# PCB_3U_Tester.net
KiCad netlist of a schematic drawn in Altium Designer
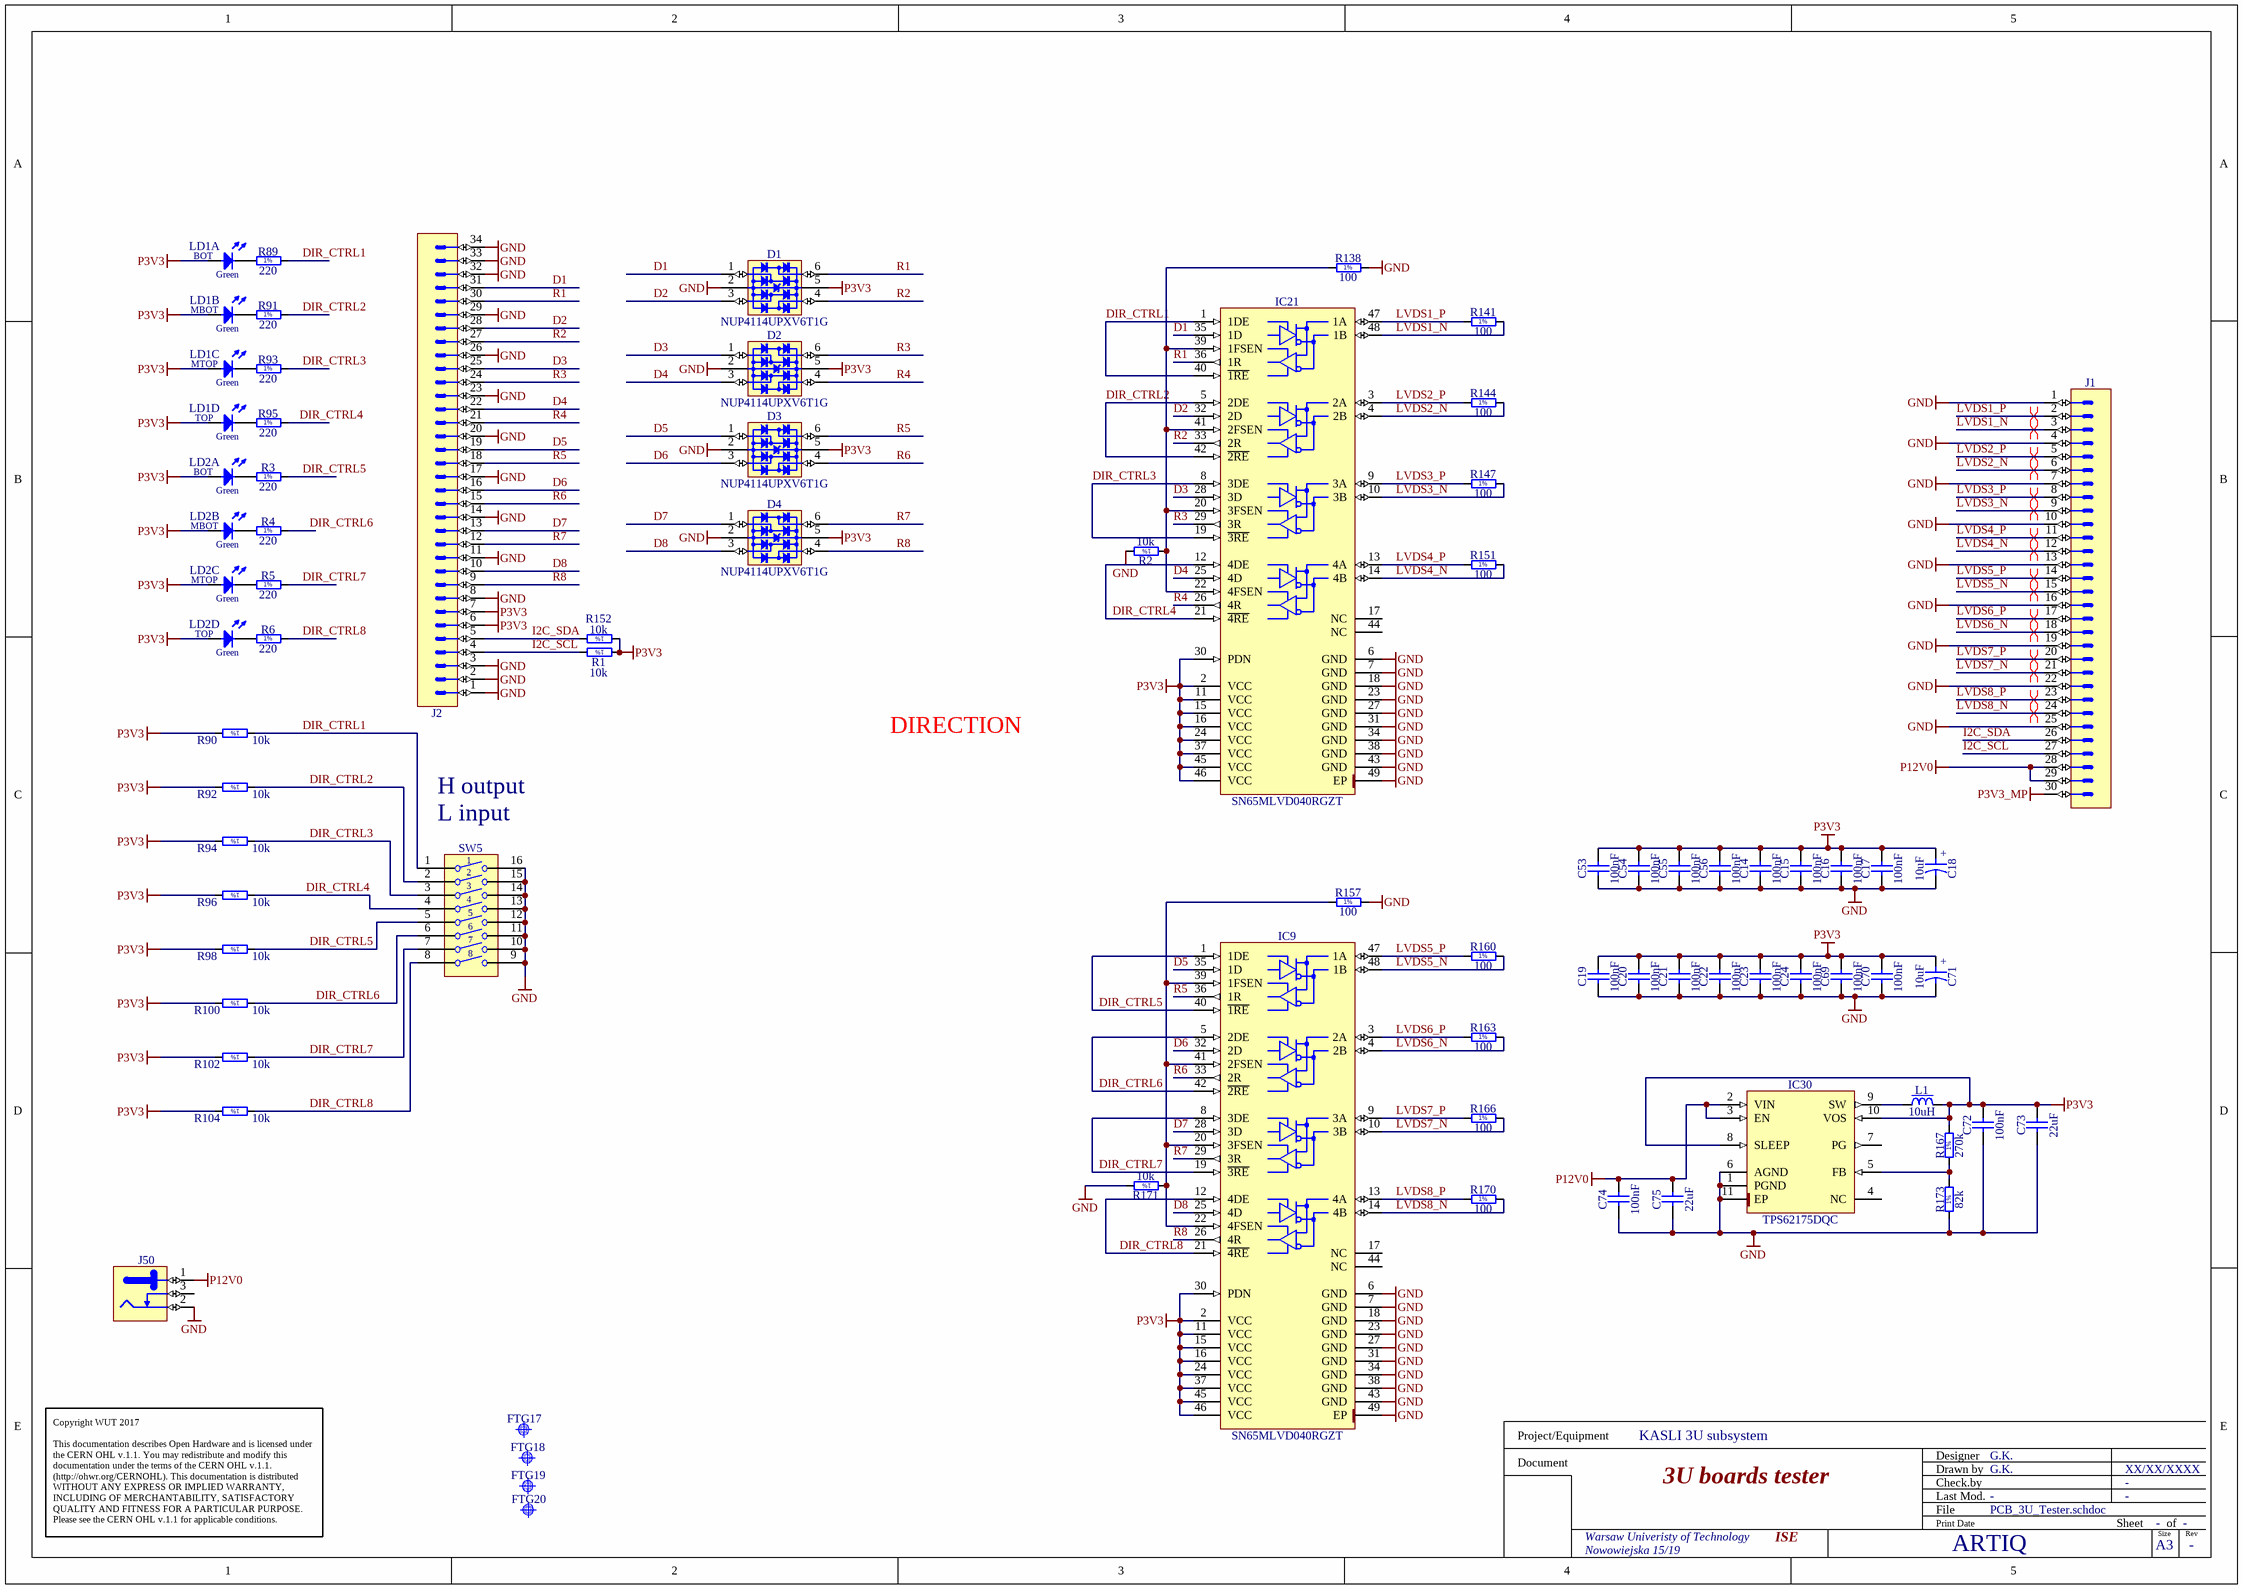
[diagram p0: PCB_3U_Tester.schdoc]

(export (version "E")
  (design (tool "Eeschema 10.0.6"))
  (components
    (comp (ref "C14")
      (value "100nF")
      (footprint "CAPC1005X55N")
      (description "Non-polarised capacitor")
      (fields
        (field (name "PART NUMBER") "CC0402_100NF_16V_10%_X5R")
        (field (name "VOLTAGE") "16V")
        (field (name "AUTHOR") "CERN DEM JLC")
      )
      (libsource (lib "Capacitors") (part "Capacitor - non polarized"))
    )
    (comp (ref "C15")
      (value "100nF")
      (footprint "CAPC1005X55N")
      (description "Non-polarised capacitor")
      (fields
        (field (name "PART NUMBER") "CC0402_100NF_16V_10%_X5R")
        (field (name "VOLTAGE") "16V")
        (field (name "AUTHOR") "CERN DEM JLC")
      )
      (libsource (lib "Capacitors") (part "Capacitor - non polarized"))
    )
    (comp (ref "C16")
      (value "100nF")
      (footprint "CAPC1005X55N")
      (description "Non-polarised capacitor")
      (fields
        (field (name "PART NUMBER") "CC0402_100NF_16V_10%_X5R")
        (field (name "VOLTAGE") "16V")
        (field (name "AUTHOR") "CERN DEM JLC")
      )
      (libsource (lib "Capacitors") (part "Capacitor - non polarized"))
    )
    (comp (ref "C17")
      (value "100nF")
      (footprint "CAPC1005X55N")
      (description "Non-polarised capacitor")
      (fields
        (field (name "PART NUMBER") "CC0402_100NF_16V_10%_X5R")
        (field (name "VOLTAGE") "16V")
        (field (name "AUTHOR") "CERN DEM JLC")
      )
      (libsource (lib "Capacitors") (part "Capacitor - non polarized"))
    )
    (comp (ref "C18")
      (value "10uF")
      (footprint "CAPAE430X540N")
      (description "Polarised capacitor")
      (fields
        (field (name "PART NUMBER") "CAE430-540_10UF_16V_20%")
        (field (name "VOLTAGE") "16V")
        (field (name "AUTHOR") "CERN DEM JLC")
      )
      (libsource (lib "Capacitors") (part "Capacitor - polarized"))
    )
    (comp (ref "C19")
      (value "100nF")
      (footprint "CAPC1005X55N")
      (description "Non-polarised capacitor")
      (fields
        (field (name "PART NUMBER") "CC0402_100NF_16V_10%_X5R")
        (field (name "VOLTAGE") "16V")
        (field (name "AUTHOR") "CERN DEM JLC")
      )
      (libsource (lib "Capacitors") (part "Capacitor - non polarized"))
    )
    (comp (ref "C20")
      (value "100nF")
      (footprint "CAPC1005X55N")
      (description "Non-polarised capacitor")
      (fields
        (field (name "PART NUMBER") "CC0402_100NF_16V_10%_X5R")
        (field (name "VOLTAGE") "16V")
        (field (name "AUTHOR") "CERN DEM JLC")
      )
      (libsource (lib "Capacitors") (part "Capacitor - non polarized"))
    )
    (comp (ref "C21")
      (value "100nF")
      (footprint "CAPC1005X55N")
      (description "Non-polarised capacitor")
      (fields
        (field (name "PART NUMBER") "CC0402_100NF_16V_10%_X5R")
        (field (name "VOLTAGE") "16V")
        (field (name "AUTHOR") "CERN DEM JLC")
      )
      (libsource (lib "Capacitors") (part "Capacitor - non polarized"))
    )
    (comp (ref "C22")
      (value "100nF")
      (footprint "CAPC1005X55N")
      (description "Non-polarised capacitor")
      (fields
        (field (name "PART NUMBER") "CC0402_100NF_16V_10%_X5R")
        (field (name "VOLTAGE") "16V")
        (field (name "AUTHOR") "CERN DEM JLC")
      )
      (libsource (lib "Capacitors") (part "Capacitor - non polarized"))
    )
    (comp (ref "C23")
      (value "100nF")
      (footprint "CAPC1005X55N")
      (description "Non-polarised capacitor")
      (fields
        (field (name "PART NUMBER") "CC0402_100NF_16V_10%_X5R")
        (field (name "VOLTAGE") "16V")
        (field (name "AUTHOR") "CERN DEM JLC")
      )
      (libsource (lib "Capacitors") (part "Capacitor - non polarized"))
    )
    (comp (ref "C24")
      (value "100nF")
      (footprint "CAPC1005X55N")
      (description "Non-polarised capacitor")
      (fields
        (field (name "PART NUMBER") "CC0402_100NF_16V_10%_X5R")
        (field (name "VOLTAGE") "16V")
        (field (name "AUTHOR") "CERN DEM JLC")
      )
      (libsource (lib "Capacitors") (part "Capacitor - non polarized"))
    )
    (comp (ref "C53")
      (value "100nF")
      (footprint "CAPC1005X55N")
      (description "Non-polarised capacitor")
      (fields
        (field (name "PART NUMBER") "CC0402_100NF_16V_10%_X5R")
        (field (name "VOLTAGE") "16V")
        (field (name "AUTHOR") "CERN DEM JLC")
      )
      (libsource (lib "Capacitors") (part "Capacitor - non polarized"))
    )
    (comp (ref "C54")
      (value "100nF")
      (footprint "CAPC1005X55N")
      (description "Non-polarised capacitor")
      (fields
        (field (name "PART NUMBER") "CC0402_100NF_16V_10%_X5R")
        (field (name "VOLTAGE") "16V")
        (field (name "AUTHOR") "CERN DEM JLC")
      )
      (libsource (lib "Capacitors") (part "Capacitor - non polarized"))
    )
    (comp (ref "C55")
      (value "100nF")
      (footprint "CAPC1005X55N")
      (description "Non-polarised capacitor")
      (fields
        (field (name "PART NUMBER") "CC0402_100NF_16V_10%_X5R")
        (field (name "VOLTAGE") "16V")
        (field (name "AUTHOR") "CERN DEM JLC")
      )
      (libsource (lib "Capacitors") (part "Capacitor - non polarized"))
    )
    (comp (ref "C56")
      (value "100nF")
      (footprint "CAPC1005X55N")
      (description "Non-polarised capacitor")
      (fields
        (field (name "PART NUMBER") "CC0402_100NF_16V_10%_X5R")
        (field (name "VOLTAGE") "16V")
        (field (name "AUTHOR") "CERN DEM JLC")
      )
      (libsource (lib "Capacitors") (part "Capacitor - non polarized"))
    )
    (comp (ref "C69")
      (value "100nF")
      (footprint "CAPC1005X55N")
      (description "Non-polarised capacitor")
      (fields
        (field (name "PART NUMBER") "CC0402_100NF_16V_10%_X5R")
        (field (name "VOLTAGE") "16V")
        (field (name "AUTHOR") "CERN DEM JLC")
      )
      (libsource (lib "Capacitors") (part "Capacitor - non polarized"))
    )
    (comp (ref "C70")
      (value "100nF")
      (footprint "CAPC1005X55N")
      (description "Non-polarised capacitor")
      (fields
        (field (name "PART NUMBER") "CC0402_100NF_16V_10%_X5R")
        (field (name "VOLTAGE") "16V")
        (field (name "AUTHOR") "CERN DEM JLC")
      )
      (libsource (lib "Capacitors") (part "Capacitor - non polarized"))
    )
    (comp (ref "C71")
      (value "10uF")
      (footprint "CAPAE430X540N")
      (description "Polarised capacitor")
      (fields
        (field (name "PART NUMBER") "CAE430-540_10UF_16V_20%")
        (field (name "VOLTAGE") "16V")
        (field (name "AUTHOR") "CERN DEM JLC")
      )
      (libsource (lib "Capacitors") (part "Capacitor - polarized"))
    )
    (comp (ref "C72")
      (value "100nF")
      (footprint "CAPC1005X55N")
      (description "Non-polarised capacitor")
      (fields
        (field (name "PART NUMBER") "CC0402_100NF_16V_10%_X5R")
        (field (name "VOLTAGE") "16V")
        (field (name "AUTHOR") "CERN DEM JLC")
      )
      (libsource (lib "Capacitors") (part "Capacitor - non polarized"))
    )
    (comp (ref "C73")
      (value "22uF")
      (footprint "CAPC2012X135N")
      (description "Non-polarised capacitor")
      (fields
        (field (name "PART NUMBER") "CC0805_22UF_16V_10%_X5R")
        (field (name "VOLTAGE") "16V")
        (field (name "AUTHOR") "CERN DEM JLC")
      )
      (libsource (lib "Capacitors") (part "Capacitor - non polarized"))
    )
    (comp (ref "C74")
      (value "100nF")
      (footprint "CAPC1005X55N")
      (description "Non-polarised capacitor")
      (fields
        (field (name "PART NUMBER") "CC0402_100NF_16V_10%_X5R")
        (field (name "VOLTAGE") "16V")
        (field (name "AUTHOR") "CERN DEM JLC")
      )
      (libsource (lib "Capacitors") (part "Capacitor - non polarized"))
    )
    (comp (ref "C75")
      (value "22uF")
      (footprint "CAPC2012X135N")
      (description "Non-polarised capacitor")
      (fields
        (field (name "PART NUMBER") "CC0805_22UF_16V_10%_X5R")
        (field (name "VOLTAGE") "16V")
        (field (name "AUTHOR") "CERN DEM JLC")
      )
      (libsource (lib "Capacitors") (part "Capacitor - non polarized"))
    )
    (comp (ref "D1")
      (value "NUP4114UPXV6T1G")
      (footprint "SOTFL50P160X60-6N")
      (fields
        (field (name "VOLTAGE") "5.5V")
        (field (name "MANUFACTURER") "ON SEMICONDUCTOR")
        (field (name "AUTHOR") "CERN DEM JLC")
      )
      (libsource (lib "ICs And Semiconductors") (part "NUP4114"))
    )
    (comp (ref "D2")
      (value "NUP4114UPXV6T1G")
      (footprint "SOTFL50P160X60-6N")
      (fields
        (field (name "VOLTAGE") "5.5V")
        (field (name "MANUFACTURER") "ON SEMICONDUCTOR")
        (field (name "AUTHOR") "CERN DEM JLC")
      )
      (libsource (lib "ICs And Semiconductors") (part "NUP4114"))
    )
    (comp (ref "D3")
      (value "NUP4114UPXV6T1G")
      (footprint "SOTFL50P160X60-6N")
      (fields
        (field (name "VOLTAGE") "5.5V")
        (field (name "MANUFACTURER") "ON SEMICONDUCTOR")
        (field (name "AUTHOR") "CERN DEM JLC")
      )
      (libsource (lib "ICs And Semiconductors") (part "NUP4114"))
    )
    (comp (ref "D4")
      (value "NUP4114UPXV6T1G")
      (footprint "SOTFL50P160X60-6N")
      (fields
        (field (name "VOLTAGE") "5.5V")
        (field (name "MANUFACTURER") "ON SEMICONDUCTOR")
        (field (name "AUTHOR") "CERN DEM JLC")
      )
      (libsource (lib "ICs And Semiconductors") (part "NUP4114"))
    )
    (comp (ref "FTG17")
      (value "Use only in PCB")
      (footprint "FIDUCIAL_TOP_C100-200")
      (description "Fiducial Target")
      (fields (field (name "PART NUMBER") "FIDUCIAL_TARGET_C100-200") (field (name "AUTHOR") "CERN DEM JLC"))
      (libsource (lib "Eletro-mechanical") (part "Fiducial Target"))
    )
    (comp (ref "FTG18")
      (value "Use only in PCB")
      (footprint "FIDUCIAL_TOP_S100-200")
      (description "Fiducial Target")
      (fields (field (name "PART NUMBER") "FIDUCIAL_TARGET_S100-200") (field (name "AUTHOR") "CERN DEM JLC"))
      (libsource (lib "Eletro-mechanical") (part "Fiducial Target"))
    )
    (comp (ref "FTG19")
      (value "Use only in PCB")
      (footprint "FIDUCIAL_TOP_S200-400")
      (description "Fiducial Target")
      (fields (field (name "PART NUMBER") "FIDUCIAL_TARGET_S200-400") (field (name "AUTHOR") "CERN DEM JLC"))
      (libsource (lib "Eletro-mechanical") (part "Fiducial Target"))
    )
    (comp (ref "FTG20")
      (value "Use only in PCB")
      (footprint "FIDUCIAL_TOP_S100-200")
      (description "Fiducial Target")
      (fields (field (name "PART NUMBER") "FIDUCIAL_TARGET_S100-200") (field (name "AUTHOR") "CERN DEM JLC"))
      (libsource (lib "Eletro-mechanical") (part "Fiducial Target"))
    )
    (comp (ref "IC9")
      (value "SN65MLVD040RGZT")
      (footprint "QFN50P700X700X100-49N-S420")
      (description "4-Channel Half-Duplex M-LVDS Line Transceiver")
      (fields (field (name "MANUFACTURER") "TEXAS INSTRUMENTS") (field (name "AUTHOR") "CERN DEM JLC"))
      (libsource (lib "ICs And Semiconductors") (part "SN65MLVD040"))
    )
    (comp (ref "IC21")
      (value "SN65MLVD040RGZT")
      (footprint "QFN50P700X700X100-49N-S420")
      (description "4-Channel Half-Duplex M-LVDS Line Transceiver")
      (fields (field (name "MANUFACTURER") "TEXAS INSTRUMENTS") (field (name "AUTHOR") "CERN DEM JLC"))
      (libsource (lib "ICs And Semiconductors") (part "SN65MLVD040"))
    )
    (comp (ref "IC30")
      (value "TPS62175DQC")
      (footprint "SON50P200X300X80-11N-R94X250")
      (description "4.75-28VDC to 1-6VDC, 500mA Step-Down Converter With Sleep Mode")
      (fields (field (name "MANUFACTURER") "TEXAS INSTRUMENTS") (field (name "AUTHOR") "CERN DEM JMW"))
      (libsource (lib "ICs And Semiconductors") (part "TPS62175"))
    )
    (comp (ref "J1")
      (value "~")
      (footprint "3M_N2530-6002RB")
      (description "Connector 30 Male")
      (fields
        (field (name "PART NUMBER") "3M_N2530-6002RB")
        (field (name "MANUFACTURER") "3M")
        (field (name "AUTHOR") "CERN DEM JLC")
      )
      (libsource (lib "Connectors") (part "Connector 30 Male"))
    )
    (comp (ref "J2")
      (value "Header 34")
      (footprint "3M_N2534-5002RB")
      (description "Connector 34 Male")
      (fields
        (field (name "PART NUMBER") "3M_N2534-5002RB")
        (field (name "MANUFACTURER") "3M")
        (field (name "AUTHOR") "CERN DEM JLC")
      )
      (libsource (lib "Connectors") (part "Connector 34 Male"))
    )
    (comp (ref "J50")
      (value "Jack")
      (footprint "CUI_PJ-102BH")
      (description "2.5 mm Center Pin, 5A, 24V Right Angle, Through Hole, Tapered Pins, DC Power Jack Connector")
      (fields
        (field (name "PART NUMBER") "CUI_PJ-102BH")
        (field (name "MANUFACTURER") "CUI INC.")
        (field (name "AUTHOR") "CERN DEM JLC")
      )
      (libsource (lib "Connectors") (part "CUI_PJ-102BH"))
    )
    (comp (ref "L1")
      (value "10uH")
      (footprint "IND_MURATA-PS_8400")
      (description "Inductor With Core")
      (fields
        (field (name "PART NUMBER") "IND_10UH_10%_MURATA-PS_8400")
        (field (name "POWER") "950mA")
        (field (name "AUTHOR") "CERN DEM JLC")
      )
      (libsource (lib "Inductors & Transformers") (part "Inductor With Magnetic core"))
    )
    (comp (ref "LD1")
      (value "Green")
      (footprint "LED_BIVAR_H485CGDL")
      (description "LED x4 Green 1C2A-BOT_3C4A_5C6A_7C8A-TOP")
      (fields
        (field (name "PART NUMBER") "LED_BIVAR_H485CGDL")
        (field (name "MANUFACTURER") "BIVAR")
        (field (name "AUTHOR") "CERN DEM JLC")
      )
      (libsource (lib "ICs And Semiconductors") (part "LED x4 Green 1C2A-BOT_3C4A_5C6A_7C8A-TOP"))
    )
    (comp (ref "LD2")
      (value "Green")
      (footprint "LED_BIVAR_H485CGDL")
      (description "LED x4 Green 1C2A-BOT_3C4A_5C6A_7C8A-TOP")
      (fields
        (field (name "PART NUMBER") "LED_BIVAR_H485CGDL")
        (field (name "MANUFACTURER") "BIVAR")
        (field (name "AUTHOR") "CERN DEM JLC")
      )
      (libsource (lib "ICs And Semiconductors") (part "LED x4 Green 1C2A-BOT_3C4A_5C6A_7C8A-TOP"))
    )
    (comp (ref "R1")
      (value "10k")
      (footprint "RESC1005X40N")
      (description "Resistor - 1%")
      (fields
        (field (name "PART NUMBER") "R0402_10K_1%_0.0625W_100PPM")
        (field (name "POWER") "0.0625W")
        (field (name "AUTHOR") "CERN DEM JLC")
      )
      (libsource (lib "Resistors") (part "Resistor - 1%"))
    )
    (comp (ref "R2")
      (value "10k")
      (footprint "RESC1005X40N")
      (description "Resistor - 1%")
      (fields
        (field (name "PART NUMBER") "R0402_10K_1%_0.0625W_100PPM")
        (field (name "POWER") "0.0625W")
        (field (name "AUTHOR") "CERN DEM JLC")
      )
      (libsource (lib "Resistors") (part "Resistor - 1%"))
    )
    (comp (ref "R3")
      (value "220")
      (footprint "RESC1608X55N")
      (description "Resistor - 1%")
      (fields
        (field (name "PART NUMBER") "R0603_220R_1%_0.1W_100PPM")
        (field (name "POWER") "0.1W")
        (field (name "AUTHOR") "CERN DEM JLC")
      )
      (libsource (lib "Resistors") (part "Resistor - 1%"))
    )
    (comp (ref "R4")
      (value "220")
      (footprint "RESC1608X55N")
      (description "Resistor - 1%")
      (fields
        (field (name "PART NUMBER") "R0603_220R_1%_0.1W_100PPM")
        (field (name "POWER") "0.1W")
        (field (name "AUTHOR") "CERN DEM JLC")
      )
      (libsource (lib "Resistors") (part "Resistor - 1%"))
    )
    (comp (ref "R5")
      (value "220")
      (footprint "RESC1608X55N")
      (description "Resistor - 1%")
      (fields
        (field (name "PART NUMBER") "R0603_220R_1%_0.1W_100PPM")
        (field (name "POWER") "0.1W")
        (field (name "AUTHOR") "CERN DEM JLC")
      )
      (libsource (lib "Resistors") (part "Resistor - 1%"))
    )
    (comp (ref "R6")
      (value "220")
      (footprint "RESC1608X55N")
      (description "Resistor - 1%")
      (fields
        (field (name "PART NUMBER") "R0603_220R_1%_0.1W_100PPM")
        (field (name "POWER") "0.1W")
        (field (name "AUTHOR") "CERN DEM JLC")
      )
      (libsource (lib "Resistors") (part "Resistor - 1%"))
    )
    (comp (ref "R89")
      (value "220")
      (footprint "RESC1608X55N")
      (description "Resistor - 1%")
      (fields
        (field (name "PART NUMBER") "R0603_220R_1%_0.1W_100PPM")
        (field (name "POWER") "0.1W")
        (field (name "AUTHOR") "CERN DEM JLC")
      )
      (libsource (lib "Resistors") (part "Resistor - 1%"))
    )
    (comp (ref "R90")
      (value "10k")
      (footprint "RESC1005X40N")
      (description "Resistor - 1%")
      (fields
        (field (name "PART NUMBER") "R0402_10K_1%_0.0625W_100PPM")
        (field (name "POWER") "0.0625W")
        (field (name "AUTHOR") "CERN DEM JLC")
      )
      (libsource (lib "Resistors") (part "Resistor - 1%"))
    )
    (comp (ref "R91")
      (value "220")
      (footprint "RESC1608X55N")
      (description "Resistor - 1%")
      (fields
        (field (name "PART NUMBER") "R0603_220R_1%_0.1W_100PPM")
        (field (name "POWER") "0.1W")
        (field (name "AUTHOR") "CERN DEM JLC")
      )
      (libsource (lib "Resistors") (part "Resistor - 1%"))
    )
    (comp (ref "R92")
      (value "10k")
      (footprint "RESC1005X40N")
      (description "Resistor - 1%")
      (fields
        (field (name "PART NUMBER") "R0402_10K_1%_0.0625W_100PPM")
        (field (name "POWER") "0.0625W")
        (field (name "AUTHOR") "CERN DEM JLC")
      )
      (libsource (lib "Resistors") (part "Resistor - 1%"))
    )
    (comp (ref "R93")
      (value "220")
      (footprint "RESC1608X55N")
      (description "Resistor - 1%")
      (fields
        (field (name "PART NUMBER") "R0603_220R_1%_0.1W_100PPM")
        (field (name "POWER") "0.1W")
        (field (name "AUTHOR") "CERN DEM JLC")
      )
      (libsource (lib "Resistors") (part "Resistor - 1%"))
    )
    (comp (ref "R94")
      (value "10k")
      (footprint "RESC1005X40N")
      (description "Resistor - 1%")
      (fields
        (field (name "PART NUMBER") "R0402_10K_1%_0.0625W_100PPM")
        (field (name "POWER") "0.0625W")
        (field (name "AUTHOR") "CERN DEM JLC")
      )
      (libsource (lib "Resistors") (part "Resistor - 1%"))
    )
    (comp (ref "R95")
      (value "220")
      (footprint "RESC1608X55N")
      (description "Resistor - 1%")
      (fields
        (field (name "PART NUMBER") "R0603_220R_1%_0.1W_100PPM")
        (field (name "POWER") "0.1W")
        (field (name "AUTHOR") "CERN DEM JLC")
      )
      (libsource (lib "Resistors") (part "Resistor - 1%"))
    )
    (comp (ref "R96")
      (value "10k")
      (footprint "RESC1005X40N")
      (description "Resistor - 1%")
      (fields
        (field (name "PART NUMBER") "R0402_10K_1%_0.0625W_100PPM")
        (field (name "POWER") "0.0625W")
        (field (name "AUTHOR") "CERN DEM JLC")
      )
      (libsource (lib "Resistors") (part "Resistor - 1%"))
    )
    (comp (ref "R98")
      (value "10k")
      (footprint "RESC1005X40N")
      (description "Resistor - 1%")
      (fields
        (field (name "PART NUMBER") "R0402_10K_1%_0.0625W_100PPM")
        (field (name "POWER") "0.0625W")
        (field (name "AUTHOR") "CERN DEM JLC")
      )
      (libsource (lib "Resistors") (part "Resistor - 1%"))
    )
    (comp (ref "R100")
      (value "10k")
      (footprint "RESC1005X40N")
      (description "Resistor - 1%")
      (fields
        (field (name "PART NUMBER") "R0402_10K_1%_0.0625W_100PPM")
        (field (name "POWER") "0.0625W")
        (field (name "AUTHOR") "CERN DEM JLC")
      )
      (libsource (lib "Resistors") (part "Resistor - 1%"))
    )
    (comp (ref "R102")
      (value "10k")
      (footprint "RESC1005X40N")
      (description "Resistor - 1%")
      (fields
        (field (name "PART NUMBER") "R0402_10K_1%_0.0625W_100PPM")
        (field (name "POWER") "0.0625W")
        (field (name "AUTHOR") "CERN DEM JLC")
      )
      (libsource (lib "Resistors") (part "Resistor - 1%"))
    )
    (comp (ref "R104")
      (value "10k")
      (footprint "RESC1005X40N")
      (description "Resistor - 1%")
      (fields
        (field (name "PART NUMBER") "R0402_10K_1%_0.0625W_100PPM")
        (field (name "POWER") "0.0625W")
        (field (name "AUTHOR") "CERN DEM JLC")
      )
      (libsource (lib "Resistors") (part "Resistor - 1%"))
    )
    (comp (ref "R138")
      (value "100")
      (footprint "RESC1005X40N")
      (description "Resistor - 1%")
      (fields
        (field (name "PART NUMBER") "R0402_100R_1%_0.1W_100PPM")
        (field (name "POWER") "0.1W")
        (field (name "AUTHOR") "CERN DEM JLC")
      )
      (libsource (lib "Resistors") (part "Resistor - 1%"))
    )
    (comp (ref "R141")
      (value "100")
      (footprint "RESC1005X40N")
      (description "Resistor - 1%")
      (fields
        (field (name "PART NUMBER") "R0402_100R_1%_0.1W_100PPM")
        (field (name "POWER") "0.1W")
        (field (name "AUTHOR") "CERN DEM JLC")
      )
      (libsource (lib "Resistors") (part "Resistor - 1%"))
    )
    (comp (ref "R144")
      (value "100")
      (footprint "RESC1005X40N")
      (description "Resistor - 1%")
      (fields
        (field (name "PART NUMBER") "R0402_100R_1%_0.1W_100PPM")
        (field (name "POWER") "0.1W")
        (field (name "AUTHOR") "CERN DEM JLC")
      )
      (libsource (lib "Resistors") (part "Resistor - 1%"))
    )
    (comp (ref "R147")
      (value "100")
      (footprint "RESC1005X40N")
      (description "Resistor - 1%")
      (fields
        (field (name "PART NUMBER") "R0402_100R_1%_0.1W_100PPM")
        (field (name "POWER") "0.1W")
        (field (name "AUTHOR") "CERN DEM JLC")
      )
      (libsource (lib "Resistors") (part "Resistor - 1%"))
    )
    (comp (ref "R151")
      (value "100")
      (footprint "RESC1005X40N")
      (description "Resistor - 1%")
      (fields
        (field (name "PART NUMBER") "R0402_100R_1%_0.1W_100PPM")
        (field (name "POWER") "0.1W")
        (field (name "AUTHOR") "CERN DEM JLC")
      )
      (libsource (lib "Resistors") (part "Resistor - 1%"))
    )
    (comp (ref "R152")
      (value "10k")
      (footprint "RESC1005X40N")
      (description "Resistor - 1%")
      (fields
        (field (name "PART NUMBER") "R0402_10K_1%_0.0625W_100PPM")
        (field (name "POWER") "0.0625W")
        (field (name "AUTHOR") "CERN DEM JLC")
      )
      (libsource (lib "Resistors") (part "Resistor - 1%"))
    )
    (comp (ref "R157")
      (value "100")
      (footprint "RESC1005X40N")
      (description "Resistor - 1%")
      (fields
        (field (name "PART NUMBER") "R0402_100R_1%_0.1W_100PPM")
        (field (name "POWER") "0.1W")
        (field (name "AUTHOR") "CERN DEM JLC")
      )
      (libsource (lib "Resistors") (part "Resistor - 1%"))
    )
    (comp (ref "R160")
      (value "100")
      (footprint "RESC1005X40N")
      (description "Resistor - 1%")
      (fields
        (field (name "PART NUMBER") "R0402_100R_1%_0.1W_100PPM")
        (field (name "POWER") "0.1W")
        (field (name "AUTHOR") "CERN DEM JLC")
      )
      (libsource (lib "Resistors") (part "Resistor - 1%"))
    )
    (comp (ref "R163")
      (value "100")
      (footprint "RESC1005X40N")
      (description "Resistor - 1%")
      (fields
        (field (name "PART NUMBER") "R0402_100R_1%_0.1W_100PPM")
        (field (name "POWER") "0.1W")
        (field (name "AUTHOR") "CERN DEM JLC")
      )
      (libsource (lib "Resistors") (part "Resistor - 1%"))
    )
    (comp (ref "R166")
      (value "100")
      (footprint "RESC1005X40N")
      (description "Resistor - 1%")
      (fields
        (field (name "PART NUMBER") "R0402_100R_1%_0.1W_100PPM")
        (field (name "POWER") "0.1W")
        (field (name "AUTHOR") "CERN DEM JLC")
      )
      (libsource (lib "Resistors") (part "Resistor - 1%"))
    )
    (comp (ref "R167")
      (value "270k")
      (footprint "RESC1608X55N")
      (description "Resistor - 1%")
      (fields
        (field (name "PART NUMBER") "R0603_270K_1%_0.1W_100PPM")
        (field (name "POWER") "0.1W")
        (field (name "AUTHOR") "CERN DEM JLC")
      )
      (libsource (lib "Resistors") (part "Resistor - 1%"))
    )
    (comp (ref "R170")
      (value "100")
      (footprint "RESC1005X40N")
      (description "Resistor - 1%")
      (fields
        (field (name "PART NUMBER") "R0402_100R_1%_0.1W_100PPM")
        (field (name "POWER") "0.1W")
        (field (name "AUTHOR") "CERN DEM JLC")
      )
      (libsource (lib "Resistors") (part "Resistor - 1%"))
    )
    (comp (ref "R171")
      (value "10k")
      (footprint "RESC1005X40N")
      (description "Resistor - 1%")
      (fields
        (field (name "PART NUMBER") "R0402_10K_1%_0.0625W_100PPM")
        (field (name "POWER") "0.0625W")
        (field (name "AUTHOR") "CERN DEM JLC")
      )
      (libsource (lib "Resistors") (part "Resistor - 1%"))
    )
    (comp (ref "R173")
      (value "82k")
      (footprint "RESC1608X55N")
      (description "Resistor - 1%")
      (fields
        (field (name "PART NUMBER") "R0603_82K_1%_0.1W_100PPM")
        (field (name "POWER") "0.1W")
        (field (name "AUTHOR") "CERN DEM JLC")
      )
      (libsource (lib "Resistors") (part "Resistor - 1%"))
    )
    (comp (ref "SW5")
      (value "Switch")
      (footprint "SW_TYCO_1-1571983-0")
      (description "8 Ways SPST DIP Switch")
      (fields
        (field (name "PART NUMBER") "SW_TYCO_1-1571983-0")
        (field (name "MANUFACTURER") "TYCO")
        (field (name "AUTHOR") "CERN DEM JLC")
      )
      (libsource (lib "Eletro-mechanical") (part "SW 8x SPST DIP Switch"))
    )
  )
  (nets
    (net (code "1") (name "/D1") (class "Default")
      (node (ref "D1") (pin "1") (pinfunction "I/O1_1") (pintype "bidirectional"))
      (node (ref "IC21") (pin "35") (pinfunction "1D_35") (pintype "input"))
      (node (ref "J2") (pin "31") (pinfunction "31_31") (pintype "bidirectional"))
    )
    (net (code "2") (name "/D2") (class "Default")
      (node (ref "D1") (pin "3") (pinfunction "I/O2_3") (pintype "bidirectional"))
      (node (ref "IC21") (pin "32") (pinfunction "2D_32") (pintype "input"))
      (node (ref "J2") (pin "28") (pinfunction "28_28") (pintype "bidirectional"))
    )
    (net (code "3") (name "/D3") (class "Default")
      (node (ref "D2") (pin "1") (pinfunction "I/O1_1") (pintype "bidirectional"))
      (node (ref "IC21") (pin "28") (pinfunction "3D_28") (pintype "input"))
      (node (ref "J2") (pin "25") (pinfunction "25_25") (pintype "bidirectional"))
    )
    (net (code "4") (name "/D4") (class "Default")
      (node (ref "D2") (pin "3") (pinfunction "I/O2_3") (pintype "bidirectional"))
      (node (ref "IC21") (pin "25") (pinfunction "4D_25") (pintype "input"))
      (node (ref "J2") (pin "22") (pinfunction "22_22") (pintype "bidirectional"))
    )
    (net (code "5") (name "/D5") (class "Default")
      (node (ref "D3") (pin "1") (pinfunction "I/O1_1") (pintype "bidirectional"))
      (node (ref "IC9") (pin "35") (pinfunction "1D_35") (pintype "input"))
      (node (ref "J2") (pin "19") (pinfunction "19_19") (pintype "bidirectional"))
    )
    (net (code "6") (name "/D6") (class "Default")
      (node (ref "D3") (pin "3") (pinfunction "I/O2_3") (pintype "bidirectional"))
      (node (ref "IC9") (pin "32") (pinfunction "2D_32") (pintype "input"))
      (node (ref "J2") (pin "16") (pinfunction "16_16") (pintype "bidirectional"))
    )
    (net (code "7") (name "/D7") (class "Default")
      (node (ref "D4") (pin "1") (pinfunction "I/O1_1") (pintype "bidirectional"))
      (node (ref "IC9") (pin "28") (pinfunction "3D_28") (pintype "input"))
      (node (ref "J2") (pin "13") (pinfunction "13_13") (pintype "bidirectional"))
    )
    (net (code "8") (name "/D8") (class "Default")
      (node (ref "D4") (pin "3") (pinfunction "I/O2_3") (pintype "bidirectional"))
      (node (ref "IC9") (pin "25") (pinfunction "4D_25") (pintype "input"))
      (node (ref "J2") (pin "10") (pinfunction "10_10") (pintype "bidirectional"))
    )
    (net (code "9") (name "/DIR_CTRL1") (class "Default")
      (node (ref "IC21") (pin "1") (pinfunction "1DE_1") (pintype "input"))
      (node (ref "IC21") (pin "40") (pinfunction "~{1RE}_40") (pintype "input"))
      (node (ref "R89") (pin "2") (pinfunction "2_2") (pintype "passive"))
      (node (ref "R90") (pin "1") (pinfunction "1_1") (pintype "passive"))
      (node (ref "SW5") (pin "1") (pinfunction "1_1") (pintype "passive"))
    )
    (net (code "10") (name "/DIR_CTRL2") (class "Default")
      (node (ref "IC21") (pin "42") (pinfunction "~{2RE}_42") (pintype "input"))
      (node (ref "IC21") (pin "5") (pinfunction "2DE_5") (pintype "input"))
      (node (ref "R91") (pin "2") (pinfunction "2_2") (pintype "passive"))
      (node (ref "R92") (pin "1") (pinfunction "1_1") (pintype "passive"))
      (node (ref "SW5") (pin "2") (pinfunction "2_2") (pintype "passive"))
    )
    (net (code "11") (name "/DIR_CTRL3") (class "Default")
      (node (ref "IC21") (pin "19") (pinfunction "~{3RE}_19") (pintype "input"))
      (node (ref "IC21") (pin "8") (pinfunction "3DE_8") (pintype "input"))
      (node (ref "R93") (pin "2") (pinfunction "2_2") (pintype "passive"))
      (node (ref "R94") (pin "1") (pinfunction "1_1") (pintype "passive"))
      (node (ref "SW5") (pin "3") (pinfunction "3_3") (pintype "passive"))
    )
    (net (code "12") (name "/DIR_CTRL4") (class "Default")
      (node (ref "IC21") (pin "12") (pinfunction "4DE_12") (pintype "input"))
      (node (ref "IC21") (pin "21") (pinfunction "~{4RE}_21") (pintype "input"))
      (node (ref "R95") (pin "2") (pinfunction "2_2") (pintype "passive"))
      (node (ref "R96") (pin "1") (pinfunction "1_1") (pintype "passive"))
      (node (ref "SW5") (pin "4") (pinfunction "4_4") (pintype "passive"))
    )
    (net (code "13") (name "/DIR_CTRL5") (class "Default")
      (node (ref "IC9") (pin "1") (pinfunction "1DE_1") (pintype "input"))
      (node (ref "IC9") (pin "40") (pinfunction "~{1RE}_40") (pintype "input"))
      (node (ref "R3") (pin "2") (pinfunction "2_2") (pintype "passive"))
      (node (ref "R98") (pin "1") (pinfunction "1_1") (pintype "passive"))
      (node (ref "SW5") (pin "5") (pinfunction "5_5") (pintype "passive"))
    )
    (net (code "14") (name "/DIR_CTRL6") (class "Default")
      (node (ref "IC9") (pin "42") (pinfunction "~{2RE}_42") (pintype "input"))
      (node (ref "IC9") (pin "5") (pinfunction "2DE_5") (pintype "input"))
      (node (ref "R100") (pin "1") (pinfunction "1_1") (pintype "passive"))
      (node (ref "R4") (pin "2") (pinfunction "2_2") (pintype "passive"))
      (node (ref "SW5") (pin "6") (pinfunction "6_6") (pintype "passive"))
    )
    (net (code "15") (name "/DIR_CTRL7") (class "Default")
      (node (ref "IC9") (pin "19") (pinfunction "~{3RE}_19") (pintype "input"))
      (node (ref "IC9") (pin "8") (pinfunction "3DE_8") (pintype "input"))
      (node (ref "R102") (pin "1") (pinfunction "1_1") (pintype "passive"))
      (node (ref "R5") (pin "2") (pinfunction "2_2") (pintype "passive"))
      (node (ref "SW5") (pin "7") (pinfunction "7_7") (pintype "passive"))
    )
    (net (code "16") (name "/DIR_CTRL8") (class "Default")
      (node (ref "IC9") (pin "12") (pinfunction "4DE_12") (pintype "input"))
      (node (ref "IC9") (pin "21") (pinfunction "~{4RE}_21") (pintype "input"))
      (node (ref "R104") (pin "1") (pinfunction "1_1") (pintype "passive"))
      (node (ref "R6") (pin "2") (pinfunction "2_2") (pintype "passive"))
      (node (ref "SW5") (pin "8") (pinfunction "8_8") (pintype "passive"))
    )
    (net (code "17") (name "/I2C_SCL") (class "Default")
      (node (ref "J1") (pin "27") (pinfunction "27_27") (pintype "bidirectional"))
      (node (ref "J2") (pin "4") (pinfunction "4_4") (pintype "bidirectional"))
      (node (ref "R1") (pin "2") (pinfunction "2_2") (pintype "passive"))
    )
    (net (code "18") (name "/I2C_SDA") (class "Default")
      (node (ref "J1") (pin "26") (pinfunction "26_26") (pintype "bidirectional"))
      (node (ref "J2") (pin "5") (pinfunction "5_5") (pintype "bidirectional"))
      (node (ref "R152") (pin "2") (pinfunction "2_2") (pintype "passive"))
    )
    (net (code "19") (name "/LVDS1_N") (class "Default")
      (node (ref "IC21") (pin "48") (pinfunction "1B_48") (pintype "bidirectional"))
      (node (ref "J1") (pin "3") (pinfunction "3_3") (pintype "bidirectional"))
      (node (ref "R141") (pin "2") (pinfunction "2_2") (pintype "passive"))
    )
    (net (code "20") (name "/LVDS1_P") (class "Default")
      (node (ref "IC21") (pin "47") (pinfunction "1A_47") (pintype "bidirectional"))
      (node (ref "J1") (pin "2") (pinfunction "2_2") (pintype "bidirectional"))
      (node (ref "R141") (pin "1") (pinfunction "1_1") (pintype "passive"))
    )
    (net (code "21") (name "/LVDS2_N") (class "Default")
      (node (ref "IC21") (pin "4") (pinfunction "2B_4") (pintype "bidirectional"))
      (node (ref "J1") (pin "6") (pinfunction "6_6") (pintype "bidirectional"))
      (node (ref "R144") (pin "2") (pinfunction "2_2") (pintype "passive"))
    )
    (net (code "22") (name "/LVDS2_P") (class "Default")
      (node (ref "IC21") (pin "3") (pinfunction "2A_3") (pintype "bidirectional"))
      (node (ref "J1") (pin "5") (pinfunction "5_5") (pintype "bidirectional"))
      (node (ref "R144") (pin "1") (pinfunction "1_1") (pintype "passive"))
    )
    (net (code "23") (name "/LVDS3_N") (class "Default")
      (node (ref "IC21") (pin "10") (pinfunction "3B_10") (pintype "bidirectional"))
      (node (ref "J1") (pin "9") (pinfunction "9_9") (pintype "bidirectional"))
      (node (ref "R147") (pin "2") (pinfunction "2_2") (pintype "passive"))
    )
    (net (code "24") (name "/LVDS3_P") (class "Default")
      (node (ref "IC21") (pin "9") (pinfunction "3A_9") (pintype "bidirectional"))
      (node (ref "J1") (pin "8") (pinfunction "8_8") (pintype "bidirectional"))
      (node (ref "R147") (pin "1") (pinfunction "1_1") (pintype "passive"))
    )
    (net (code "25") (name "/LVDS4_N") (class "Default")
      (node (ref "IC21") (pin "14") (pinfunction "4B_14") (pintype "bidirectional"))
      (node (ref "J1") (pin "12") (pinfunction "12_12") (pintype "bidirectional"))
      (node (ref "R151") (pin "2") (pinfunction "2_2") (pintype "passive"))
    )
    (net (code "26") (name "/LVDS4_P") (class "Default")
      (node (ref "IC21") (pin "13") (pinfunction "4A_13") (pintype "bidirectional"))
      (node (ref "J1") (pin "11") (pinfunction "11_11") (pintype "bidirectional"))
      (node (ref "R151") (pin "1") (pinfunction "1_1") (pintype "passive"))
    )
    (net (code "27") (name "/LVDS5_N") (class "Default")
      (node (ref "IC9") (pin "48") (pinfunction "1B_48") (pintype "bidirectional"))
      (node (ref "J1") (pin "15") (pinfunction "15_15") (pintype "bidirectional"))
      (node (ref "R160") (pin "2") (pinfunction "2_2") (pintype "passive"))
    )
    (net (code "28") (name "/LVDS5_P") (class "Default")
      (node (ref "IC9") (pin "47") (pinfunction "1A_47") (pintype "bidirectional"))
      (node (ref "J1") (pin "14") (pinfunction "14_14") (pintype "bidirectional"))
      (node (ref "R160") (pin "1") (pinfunction "1_1") (pintype "passive"))
    )
    (net (code "29") (name "/LVDS6_N") (class "Default")
      (node (ref "IC9") (pin "4") (pinfunction "2B_4") (pintype "bidirectional"))
      (node (ref "J1") (pin "18") (pinfunction "18_18") (pintype "bidirectional"))
      (node (ref "R163") (pin "2") (pinfunction "2_2") (pintype "passive"))
    )
    (net (code "30") (name "/LVDS6_P") (class "Default")
      (node (ref "IC9") (pin "3") (pinfunction "2A_3") (pintype "bidirectional"))
      (node (ref "J1") (pin "17") (pinfunction "17_17") (pintype "bidirectional"))
      (node (ref "R163") (pin "1") (pinfunction "1_1") (pintype "passive"))
    )
    (net (code "31") (name "/LVDS7_N") (class "Default")
      (node (ref "IC9") (pin "10") (pinfunction "3B_10") (pintype "bidirectional"))
      (node (ref "J1") (pin "21") (pinfunction "21_21") (pintype "bidirectional"))
      (node (ref "R166") (pin "2") (pinfunction "2_2") (pintype "passive"))
    )
    (net (code "32") (name "/LVDS7_P") (class "Default")
      (node (ref "IC9") (pin "9") (pinfunction "3A_9") (pintype "bidirectional"))
      (node (ref "J1") (pin "20") (pinfunction "20_20") (pintype "bidirectional"))
      (node (ref "R166") (pin "1") (pinfunction "1_1") (pintype "passive"))
    )
    (net (code "33") (name "/LVDS8_N") (class "Default")
      (node (ref "IC9") (pin "14") (pinfunction "4B_14") (pintype "bidirectional"))
      (node (ref "J1") (pin "24") (pinfunction "24_24") (pintype "bidirectional"))
      (node (ref "R170") (pin "2") (pinfunction "2_2") (pintype "passive"))
    )
    (net (code "34") (name "/LVDS8_P") (class "Default")
      (node (ref "IC9") (pin "13") (pinfunction "4A_13") (pintype "bidirectional"))
      (node (ref "J1") (pin "23") (pinfunction "23_23") (pintype "bidirectional"))
      (node (ref "R170") (pin "1") (pinfunction "1_1") (pintype "passive"))
    )
    (net (code "35") (name "/R1") (class "Default")
      (node (ref "D1") (pin "6") (pinfunction "I/O4_6") (pintype "bidirectional"))
      (node (ref "IC21") (pin "36") (pinfunction "1R_36") (pintype "output"))
      (node (ref "J2") (pin "30") (pinfunction "30_30") (pintype "bidirectional"))
    )
    (net (code "36") (name "/R2") (class "Default")
      (node (ref "D1") (pin "4") (pinfunction "I/O3_4") (pintype "bidirectional"))
      (node (ref "IC21") (pin "33") (pinfunction "2R_33") (pintype "output"))
      (node (ref "J2") (pin "27") (pinfunction "27_27") (pintype "bidirectional"))
    )
    (net (code "37") (name "/R3") (class "Default")
      (node (ref "D2") (pin "6") (pinfunction "I/O4_6") (pintype "bidirectional"))
      (node (ref "IC21") (pin "29") (pinfunction "3R_29") (pintype "output"))
      (node (ref "J2") (pin "24") (pinfunction "24_24") (pintype "bidirectional"))
    )
    (net (code "38") (name "/R4") (class "Default")
      (node (ref "D2") (pin "4") (pinfunction "I/O3_4") (pintype "bidirectional"))
      (node (ref "IC21") (pin "26") (pinfunction "4R_26") (pintype "output"))
      (node (ref "J2") (pin "21") (pinfunction "21_21") (pintype "bidirectional"))
    )
    (net (code "39") (name "/R5") (class "Default")
      (node (ref "D3") (pin "6") (pinfunction "I/O4_6") (pintype "bidirectional"))
      (node (ref "IC9") (pin "36") (pinfunction "1R_36") (pintype "output"))
      (node (ref "J2") (pin "18") (pinfunction "18_18") (pintype "bidirectional"))
    )
    (net (code "40") (name "/R6") (class "Default")
      (node (ref "D3") (pin "4") (pinfunction "I/O3_4") (pintype "bidirectional"))
      (node (ref "IC9") (pin "33") (pinfunction "2R_33") (pintype "output"))
      (node (ref "J2") (pin "15") (pinfunction "15_15") (pintype "bidirectional"))
    )
    (net (code "41") (name "/R7") (class "Default")
      (node (ref "D4") (pin "6") (pinfunction "I/O4_6") (pintype "bidirectional"))
      (node (ref "IC9") (pin "29") (pinfunction "3R_29") (pintype "output"))
      (node (ref "J2") (pin "12") (pinfunction "12_12") (pintype "bidirectional"))
    )
    (net (code "42") (name "/R8") (class "Default")
      (node (ref "D4") (pin "4") (pinfunction "I/O3_4") (pintype "bidirectional"))
      (node (ref "IC9") (pin "26") (pinfunction "4R_26") (pintype "output"))
      (node (ref "J2") (pin "9") (pinfunction "9_9") (pintype "bidirectional"))
    )
    (net (code "43") (name "GND") (class "Default")
      (node (ref "C14") (pin "1") (pinfunction "1_1") (pintype "passive"))
      (node (ref "C15") (pin "1") (pinfunction "1_1") (pintype "passive"))
      (node (ref "C16") (pin "1") (pinfunction "1_1") (pintype "passive"))
      (node (ref "C17") (pin "1") (pinfunction "1_1") (pintype "passive"))
      (node (ref "C18") (pin "2") (pinfunction "2_2") (pintype "passive"))
      (node (ref "C19") (pin "1") (pinfunction "1_1") (pintype "passive"))
      (node (ref "C20") (pin "1") (pinfunction "1_1") (pintype "passive"))
      (node (ref "C21") (pin "1") (pinfunction "1_1") (pintype "passive"))
      (node (ref "C22") (pin "1") (pinfunction "1_1") (pintype "passive"))
      (node (ref "C23") (pin "1") (pinfunction "1_1") (pintype "passive"))
      (node (ref "C24") (pin "1") (pinfunction "1_1") (pintype "passive"))
      (node (ref "C53") (pin "1") (pinfunction "1_1") (pintype "passive"))
      (node (ref "C54") (pin "1") (pinfunction "1_1") (pintype "passive"))
      (node (ref "C55") (pin "1") (pinfunction "1_1") (pintype "passive"))
      (node (ref "C56") (pin "1") (pinfunction "1_1") (pintype "passive"))
      (node (ref "C69") (pin "1") (pinfunction "1_1") (pintype "passive"))
      (node (ref "C70") (pin "1") (pinfunction "1_1") (pintype "passive"))
      (node (ref "C71") (pin "2") (pinfunction "2_2") (pintype "passive"))
      (node (ref "C72") (pin "1") (pinfunction "1_1") (pintype "passive"))
      (node (ref "C73") (pin "1") (pinfunction "1_1") (pintype "passive"))
      (node (ref "C74") (pin "1") (pinfunction "1_1") (pintype "passive"))
      (node (ref "C75") (pin "1") (pinfunction "1_1") (pintype "passive"))
      (node (ref "D1") (pin "2") (pinfunction "GND_2") (pintype "power_in"))
      (node (ref "D2") (pin "2") (pinfunction "GND_2") (pintype "power_in"))
      (node (ref "D3") (pin "2") (pinfunction "GND_2") (pintype "power_in"))
      (node (ref "D4") (pin "2") (pinfunction "GND_2") (pintype "power_in"))
      (node (ref "IC21") (pin "18") (pinfunction "GND_18") (pintype "power_in"))
      (node (ref "IC21") (pin "23") (pinfunction "GND_23") (pintype "power_in"))
      (node (ref "IC21") (pin "27") (pinfunction "GND_27") (pintype "power_in"))
      (node (ref "IC21") (pin "31") (pinfunction "GND_31") (pintype "power_in"))
      (node (ref "IC21") (pin "34") (pinfunction "GND_34") (pintype "power_in"))
      (node (ref "IC21") (pin "38") (pinfunction "GND_38") (pintype "power_in"))
      (node (ref "IC21") (pin "43") (pinfunction "GND_43") (pintype "power_in"))
      (node (ref "IC21") (pin "49") (pinfunction "EP_49") (pintype "power_in"))
      (node (ref "IC21") (pin "6") (pinfunction "GND_6") (pintype "power_in"))
      (node (ref "IC21") (pin "7") (pinfunction "GND_7") (pintype "power_in"))
      (node (ref "IC30") (pin "1") (pinfunction "PGND_1") (pintype "power_in"))
      (node (ref "IC30") (pin "11") (pinfunction "EP_11") (pintype "power_in"))
      (node (ref "IC30") (pin "6") (pinfunction "AGND_6") (pintype "power_in"))
      (node (ref "IC9") (pin "18") (pinfunction "GND_18") (pintype "power_in"))
      (node (ref "IC9") (pin "23") (pinfunction "GND_23") (pintype "power_in"))
      (node (ref "IC9") (pin "27") (pinfunction "GND_27") (pintype "power_in"))
      (node (ref "IC9") (pin "31") (pinfunction "GND_31") (pintype "power_in"))
      (node (ref "IC9") (pin "34") (pinfunction "GND_34") (pintype "power_in"))
      (node (ref "IC9") (pin "38") (pinfunction "GND_38") (pintype "power_in"))
      (node (ref "IC9") (pin "43") (pinfunction "GND_43") (pintype "power_in"))
      (node (ref "IC9") (pin "49") (pinfunction "EP_49") (pintype "power_in"))
      (node (ref "IC9") (pin "6") (pinfunction "GND_6") (pintype "power_in"))
      (node (ref "IC9") (pin "7") (pinfunction "GND_7") (pintype "power_in"))
      (node (ref "J1") (pin "1") (pinfunction "1_1") (pintype "bidirectional"))
      (node (ref "J1") (pin "10") (pinfunction "10_10") (pintype "bidirectional"))
      (node (ref "J1") (pin "13") (pinfunction "13_13") (pintype "bidirectional"))
      (node (ref "J1") (pin "16") (pinfunction "16_16") (pintype "bidirectional"))
      (node (ref "J1") (pin "19") (pinfunction "19_19") (pintype "bidirectional"))
      (node (ref "J1") (pin "22") (pinfunction "22_22") (pintype "bidirectional"))
      (node (ref "J1") (pin "25") (pinfunction "25_25") (pintype "bidirectional"))
      (node (ref "J1") (pin "4") (pinfunction "4_4") (pintype "bidirectional"))
      (node (ref "J1") (pin "7") (pinfunction "7_7") (pintype "bidirectional"))
      (node (ref "J2") (pin "1") (pinfunction "1_1") (pintype "bidirectional"))
      (node (ref "J2") (pin "11") (pinfunction "11_11") (pintype "bidirectional"))
      (node (ref "J2") (pin "14") (pinfunction "14_14") (pintype "bidirectional"))
      (node (ref "J2") (pin "17") (pinfunction "17_17") (pintype "bidirectional"))
      (node (ref "J2") (pin "2") (pinfunction "2_2") (pintype "bidirectional"))
      (node (ref "J2") (pin "20") (pinfunction "20_20") (pintype "bidirectional"))
      (node (ref "J2") (pin "23") (pinfunction "23_23") (pintype "bidirectional"))
      (node (ref "J2") (pin "26") (pinfunction "26_26") (pintype "bidirectional"))
      (node (ref "J2") (pin "29") (pinfunction "29_29") (pintype "bidirectional"))
      (node (ref "J2") (pin "3") (pinfunction "3_3") (pintype "bidirectional"))
      (node (ref "J2") (pin "32") (pinfunction "32_32") (pintype "bidirectional"))
      (node (ref "J2") (pin "33") (pinfunction "33_33") (pintype "bidirectional"))
      (node (ref "J2") (pin "34") (pinfunction "34_34") (pintype "bidirectional"))
      (node (ref "J2") (pin "8") (pinfunction "8_8") (pintype "bidirectional"))
      (node (ref "J50") (pin "2") (pinfunction "2_2") (pintype "bidirectional"))
      (node (ref "R138") (pin "2") (pinfunction "2_2") (pintype "passive"))
      (node (ref "R157") (pin "2") (pinfunction "2_2") (pintype "passive"))
      (node (ref "R171") (pin "2") (pinfunction "2_2") (pintype "passive"))
      (node (ref "R173") (pin "1") (pinfunction "1_1") (pintype "passive"))
      (node (ref "R2") (pin "2") (pinfunction "2_2") (pintype "passive"))
      (node (ref "SW5") (pin "10") (pinfunction "10_10") (pintype "passive"))
      (node (ref "SW5") (pin "11") (pinfunction "11_11") (pintype "passive"))
      (node (ref "SW5") (pin "12") (pinfunction "12_12") (pintype "passive"))
      (node (ref "SW5") (pin "13") (pinfunction "13_13") (pintype "passive"))
      (node (ref "SW5") (pin "14") (pinfunction "14_14") (pintype "passive"))
      (node (ref "SW5") (pin "15") (pinfunction "15_15") (pintype "passive"))
      (node (ref "SW5") (pin "16") (pinfunction "16_16") (pintype "passive"))
      (node (ref "SW5") (pin "9") (pinfunction "9_9") (pintype "passive"))
    )
    (net (code "44") (name "Net-(IC9-1FSEN)") (class "Default")
      (node (ref "IC9") (pin "20") (pinfunction "3FSEN_20") (pintype "input"))
      (node (ref "IC9") (pin "22") (pinfunction "4FSEN_22") (pintype "input"))
      (node (ref "IC9") (pin "39") (pinfunction "1FSEN_39") (pintype "input"))
      (node (ref "IC9") (pin "41") (pinfunction "2FSEN_41") (pintype "input"))
      (node (ref "R157") (pin "1") (pinfunction "1_1") (pintype "passive"))
      (node (ref "R171") (pin "1") (pinfunction "1_1") (pintype "passive"))
    )
    (net (code "45") (name "Net-(IC21-1FSEN)") (class "Default")
      (node (ref "IC21") (pin "20") (pinfunction "3FSEN_20") (pintype "input"))
      (node (ref "IC21") (pin "22") (pinfunction "4FSEN_22") (pintype "input"))
      (node (ref "IC21") (pin "39") (pinfunction "1FSEN_39") (pintype "input"))
      (node (ref "IC21") (pin "41") (pinfunction "2FSEN_41") (pintype "input"))
      (node (ref "R138") (pin "1") (pinfunction "1_1") (pintype "passive"))
      (node (ref "R2") (pin "1") (pinfunction "1_1") (pintype "passive"))
    )
    (net (code "46") (name "Net-(IC30-FB)") (class "Default")
      (node (ref "IC30") (pin "5") (pinfunction "FB_5") (pintype "input"))
      (node (ref "R167") (pin "1") (pinfunction "1_1") (pintype "passive"))
      (node (ref "R173") (pin "2") (pinfunction "2_2") (pintype "passive"))
    )
    (net (code "47") (name "Net-(IC30-SW)") (class "Default")
      (node (ref "IC30") (pin "9") (pinfunction "SW_9") (pintype "output"))
      (node (ref "L1") (pin "1") (pinfunction "1_1") (pintype "passive"))
    )
    (net (code "48") (name "Net-(LD1A-C)") (class "Default")
      (node (ref "LD1") (pin "1") (pinfunction "C_1") (pintype "passive"))
      (node (ref "R89") (pin "1") (pinfunction "1_1") (pintype "passive"))
    )
    (net (code "49") (name "Net-(LD1B-C)") (class "Default")
      (node (ref "LD1") (pin "3") (pinfunction "C_3") (pintype "passive"))
      (node (ref "R91") (pin "1") (pinfunction "1_1") (pintype "passive"))
    )
    (net (code "50") (name "Net-(LD1C-C)") (class "Default")
      (node (ref "LD1") (pin "5") (pinfunction "C_5") (pintype "passive"))
      (node (ref "R93") (pin "1") (pinfunction "1_1") (pintype "passive"))
    )
    (net (code "51") (name "Net-(LD1D-C)") (class "Default")
      (node (ref "LD1") (pin "7") (pinfunction "C_7") (pintype "passive"))
      (node (ref "R95") (pin "1") (pinfunction "1_1") (pintype "passive"))
    )
    (net (code "52") (name "Net-(LD2A-C)") (class "Default")
      (node (ref "LD2") (pin "1") (pinfunction "C_1") (pintype "passive"))
      (node (ref "R3") (pin "1") (pinfunction "1_1") (pintype "passive"))
    )
    (net (code "53") (name "Net-(LD2B-C)") (class "Default")
      (node (ref "LD2") (pin "3") (pinfunction "C_3") (pintype "passive"))
      (node (ref "R4") (pin "1") (pinfunction "1_1") (pintype "passive"))
    )
    (net (code "54") (name "Net-(LD2C-C)") (class "Default")
      (node (ref "LD2") (pin "5") (pinfunction "C_5") (pintype "passive"))
      (node (ref "R5") (pin "1") (pinfunction "1_1") (pintype "passive"))
    )
    (net (code "55") (name "Net-(LD2D-C)") (class "Default")
      (node (ref "LD2") (pin "7") (pinfunction "C_7") (pintype "passive"))
      (node (ref "R6") (pin "1") (pinfunction "1_1") (pintype "passive"))
    )
    (net (code "56") (name "P3V3") (class "Default")
      (node (ref "C14") (pin "2") (pinfunction "2_2") (pintype "passive"))
      (node (ref "C15") (pin "2") (pinfunction "2_2") (pintype "passive"))
      (node (ref "C16") (pin "2") (pinfunction "2_2") (pintype "passive"))
      (node (ref "C17") (pin "2") (pinfunction "2_2") (pintype "passive"))
      (node (ref "C18") (pin "1") (pinfunction "1_1") (pintype "passive"))
      (node (ref "C19") (pin "2") (pinfunction "2_2") (pintype "passive"))
      (node (ref "C20") (pin "2") (pinfunction "2_2") (pintype "passive"))
      (node (ref "C21") (pin "2") (pinfunction "2_2") (pintype "passive"))
      (node (ref "C22") (pin "2") (pinfunction "2_2") (pintype "passive"))
      (node (ref "C23") (pin "2") (pinfunction "2_2") (pintype "passive"))
      (node (ref "C24") (pin "2") (pinfunction "2_2") (pintype "passive"))
      (node (ref "C53") (pin "2") (pinfunction "2_2") (pintype "passive"))
      (node (ref "C54") (pin "2") (pinfunction "2_2") (pintype "passive"))
      (node (ref "C55") (pin "2") (pinfunction "2_2") (pintype "passive"))
      (node (ref "C56") (pin "2") (pinfunction "2_2") (pintype "passive"))
      (node (ref "C69") (pin "2") (pinfunction "2_2") (pintype "passive"))
      (node (ref "C70") (pin "2") (pinfunction "2_2") (pintype "passive"))
      (node (ref "C71") (pin "1") (pinfunction "1_1") (pintype "passive"))
      (node (ref "C72") (pin "2") (pinfunction "2_2") (pintype "passive"))
      (node (ref "C73") (pin "2") (pinfunction "2_2") (pintype "passive"))
      (node (ref "D1") (pin "5") (pinfunction "VBUS_5") (pintype "power_in"))
      (node (ref "D2") (pin "5") (pinfunction "VBUS_5") (pintype "power_in"))
      (node (ref "D3") (pin "5") (pinfunction "VBUS_5") (pintype "power_in"))
      (node (ref "D4") (pin "5") (pinfunction "VBUS_5") (pintype "power_in"))
      (node (ref "IC21") (pin "11") (pinfunction "VCC_11") (pintype "power_in"))
      (node (ref "IC21") (pin "15") (pinfunction "VCC_15") (pintype "power_in"))
      (node (ref "IC21") (pin "16") (pinfunction "VCC_16") (pintype "power_in"))
      (node (ref "IC21") (pin "2") (pinfunction "VCC_2") (pintype "power_in"))
      (node (ref "IC21") (pin "24") (pinfunction "VCC_24") (pintype "power_in"))
      (node (ref "IC21") (pin "30") (pinfunction "PDN_30") (pintype "input"))
      (node (ref "IC21") (pin "37") (pinfunction "VCC_37") (pintype "power_in"))
      (node (ref "IC21") (pin "45") (pinfunction "VCC_45") (pintype "power_in"))
      (node (ref "IC21") (pin "46") (pinfunction "VCC_46") (pintype "power_in"))
      (node (ref "IC30") (pin "10") (pinfunction "VOS_10") (pintype "input"))
      (node (ref "IC30") (pin "8") (pinfunction "SLEEP_8") (pintype "input"))
      (node (ref "IC9") (pin "11") (pinfunction "VCC_11") (pintype "power_in"))
      (node (ref "IC9") (pin "15") (pinfunction "VCC_15") (pintype "power_in"))
      (node (ref "IC9") (pin "16") (pinfunction "VCC_16") (pintype "power_in"))
      (node (ref "IC9") (pin "2") (pinfunction "VCC_2") (pintype "power_in"))
      (node (ref "IC9") (pin "24") (pinfunction "VCC_24") (pintype "power_in"))
      (node (ref "IC9") (pin "30") (pinfunction "PDN_30") (pintype "input"))
      (node (ref "IC9") (pin "37") (pinfunction "VCC_37") (pintype "power_in"))
      (node (ref "IC9") (pin "45") (pinfunction "VCC_45") (pintype "power_in"))
      (node (ref "IC9") (pin "46") (pinfunction "VCC_46") (pintype "power_in"))
      (node (ref "J2") (pin "6") (pinfunction "6_6") (pintype "bidirectional"))
      (node (ref "J2") (pin "7") (pinfunction "7_7") (pintype "bidirectional"))
      (node (ref "L1") (pin "2") (pinfunction "2_2") (pintype "passive"))
      (node (ref "LD1") (pin "2") (pinfunction "A_2") (pintype "passive"))
      (node (ref "LD1") (pin "4") (pinfunction "A_4") (pintype "passive"))
      (node (ref "LD1") (pin "6") (pinfunction "A_6") (pintype "passive"))
      (node (ref "LD1") (pin "8") (pinfunction "A_8") (pintype "passive"))
      (node (ref "LD2") (pin "2") (pinfunction "A_2") (pintype "passive"))
      (node (ref "LD2") (pin "4") (pinfunction "A_4") (pintype "passive"))
      (node (ref "LD2") (pin "6") (pinfunction "A_6") (pintype "passive"))
      (node (ref "LD2") (pin "8") (pinfunction "A_8") (pintype "passive"))
      (node (ref "R1") (pin "1") (pinfunction "1_1") (pintype "passive"))
      (node (ref "R100") (pin "2") (pinfunction "2_2") (pintype "passive"))
      (node (ref "R102") (pin "2") (pinfunction "2_2") (pintype "passive"))
      (node (ref "R104") (pin "2") (pinfunction "2_2") (pintype "passive"))
      (node (ref "R152") (pin "1") (pinfunction "1_1") (pintype "passive"))
      (node (ref "R167") (pin "2") (pinfunction "2_2") (pintype "passive"))
      (node (ref "R90") (pin "2") (pinfunction "2_2") (pintype "passive"))
      (node (ref "R92") (pin "2") (pinfunction "2_2") (pintype "passive"))
      (node (ref "R94") (pin "2") (pinfunction "2_2") (pintype "passive"))
      (node (ref "R96") (pin "2") (pinfunction "2_2") (pintype "passive"))
      (node (ref "R98") (pin "2") (pinfunction "2_2") (pintype "passive"))
    )
    (net (code "57") (name "P3V3_MP") (class "Default")
      (node (ref "J1") (pin "30") (pinfunction "30_30") (pintype "bidirectional"))
    )
    (net (code "58") (name "P12V0") (class "Default")
      (node (ref "C74") (pin "2") (pinfunction "2_2") (pintype "passive"))
      (node (ref "C75") (pin "2") (pinfunction "2_2") (pintype "passive"))
      (node (ref "IC30") (pin "2") (pinfunction "VIN_2") (pintype "input"))
      (node (ref "IC30") (pin "3") (pinfunction "EN_3") (pintype "input"))
      (node (ref "J1") (pin "28") (pinfunction "28_28") (pintype "bidirectional"))
      (node (ref "J1") (pin "29") (pinfunction "29_29") (pintype "bidirectional"))
      (node (ref "J50") (pin "1") (pinfunction "1_1") (pintype "bidirectional"))
    )
    (net (code "59") (name "unconnected-(IC9-NC-Pad17)") (class "Default")
      (node (ref "IC9") (pin "17") (pinfunction "NC_17") (pintype "passive"))
    )
    (net (code "60") (name "unconnected-(IC9-NC-Pad44)") (class "Default")
      (node (ref "IC9") (pin "44") (pinfunction "NC_44") (pintype "passive"))
    )
    (net (code "61") (name "unconnected-(IC21-NC-Pad17)") (class "Default")
      (node (ref "IC21") (pin "17") (pinfunction "NC_17") (pintype "passive"))
    )
    (net (code "62") (name "unconnected-(IC21-NC-Pad44)") (class "Default")
      (node (ref "IC21") (pin "44") (pinfunction "NC_44") (pintype "passive"))
    )
    (net (code "63") (name "unconnected-(IC30-NC-Pad4)") (class "Default")
      (node (ref "IC30") (pin "4") (pinfunction "NC_4") (pintype "passive"))
    )
    (net (code "64") (name "unconnected-(IC30-PG-Pad7)") (class "Default")
      (node (ref "IC30") (pin "7") (pinfunction "PG_7") (pintype "output"))
    )
    (net (code "65") (name "unconnected-(J50-Pad3)") (class "Default")
      (node (ref "J50") (pin "3") (pinfunction "3_3") (pintype "bidirectional"))
    )
  )
)
